# blank_rev_1.net
KiCad netlist of a schematic drawn in EAGLE
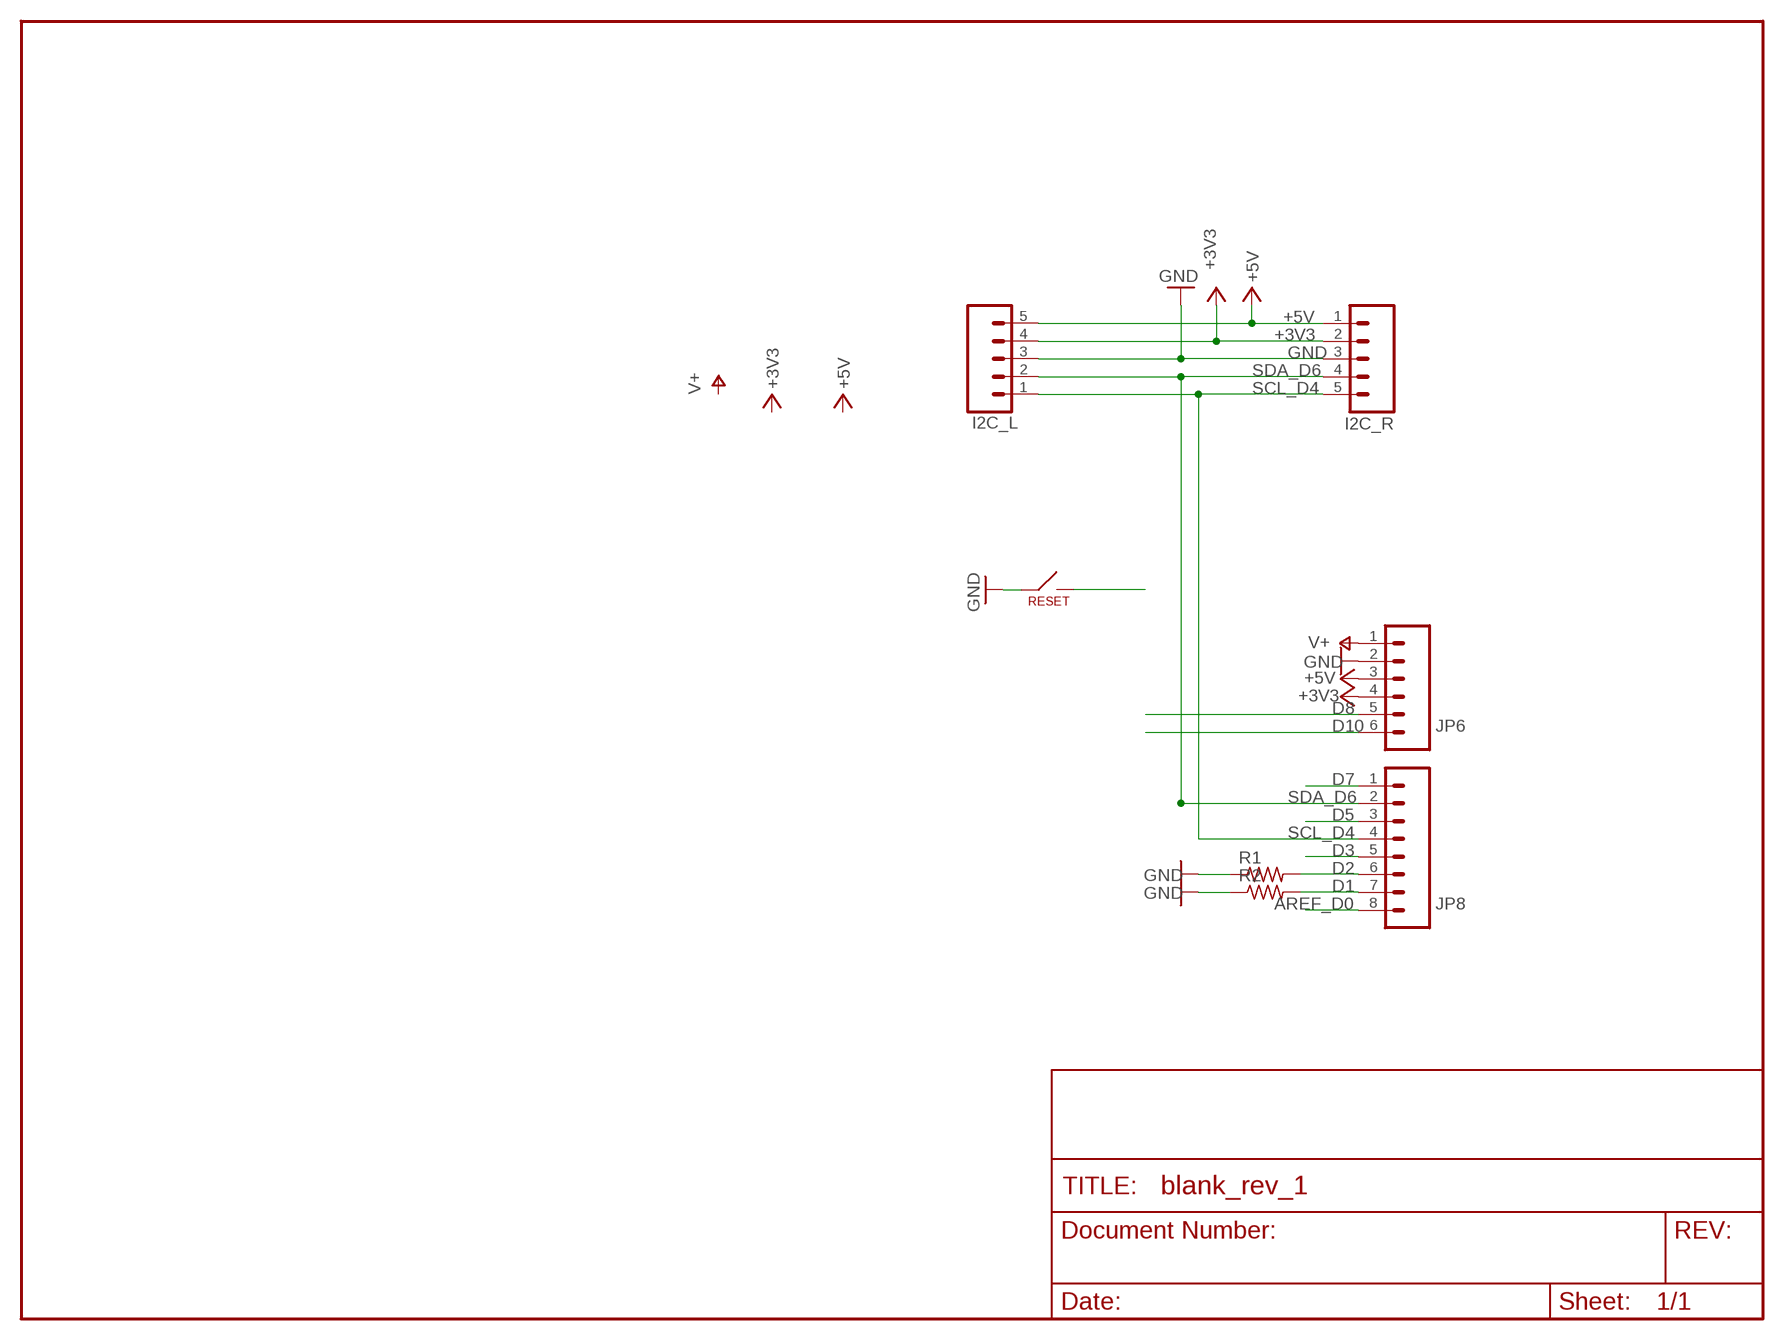
[diagram p0: schematic, sheet 1]

(export (version "E")
  (design (tool "Eeschema 10.0.6"))
  (components
    (comp (ref "I2C_L")
      (value "M05PTH")
      (footprint "eagle-import:1X05")
      (libsource (lib "eagle-import") (part "M05PTH"))
    )
    (comp (ref "I2C_R")
      (value "M05PTH")
      (footprint "eagle-import:1X05")
      (libsource (lib "eagle-import") (part "M05PTH"))
    )
    (comp (ref "JP6")
      (value "M06SIP")
      (footprint "eagle-import:1X06")
      (libsource (lib "eagle-import") (part "M06SIP"))
    )
    (comp (ref "JP8")
      (value "M081X08")
      (footprint "eagle-import:1X08")
      (libsource (lib "eagle-import") (part "M081X08"))
    )
    (comp (ref "R1")
      (value "R-US_0204/2V")
      (footprint "eagle-import:0204V")
      (libsource (lib "eagle-import") (part "R-US_0204/2V"))
    )
    (comp (ref "R2")
      (value "R-US_0204/2V")
      (footprint "eagle-import:0204V")
      (libsource (lib "eagle-import") (part "R-US_0204/2V"))
    )
    (comp (ref "RESET")
      (value "PTS635_SWITCH")
      (footprint "eagle-import:PTS635_SWITCH")
      (libsource (lib "eagle-import") (part "PTS635_SWITCH"))
    )
  )
  (nets
    (net (code "1") (name "+3V3") (class "Default")
      (node (ref "I2C_L") (pin "4") (pinfunction "4_4") (pintype "passive"))
      (node (ref "I2C_R") (pin "2") (pinfunction "2_2") (pintype "passive"))
      (node (ref "JP6") (pin "4") (pinfunction "4_4") (pintype "passive"))
    )
    (net (code "2") (name "+5V") (class "Default")
      (node (ref "I2C_L") (pin "5") (pinfunction "5_5") (pintype "passive"))
      (node (ref "I2C_R") (pin "1") (pinfunction "1_1") (pintype "passive"))
      (node (ref "JP6") (pin "3") (pinfunction "3_3") (pintype "passive"))
    )
    (net (code "3") (name "/AREF_D0") (class "Default")
      (node (ref "JP8") (pin "8") (pinfunction "8_8") (pintype "passive"))
    )
    (net (code "4") (name "/D1") (class "Default")
      (node (ref "JP8") (pin "7") (pinfunction "7_7") (pintype "passive"))
      (node (ref "R2") (pin "2") (pinfunction "2_2") (pintype "passive"))
    )
    (net (code "5") (name "/D2") (class "Default")
      (node (ref "JP8") (pin "6") (pinfunction "6_6") (pintype "passive"))
      (node (ref "R1") (pin "2") (pinfunction "2_2") (pintype "passive"))
    )
    (net (code "6") (name "/D3") (class "Default")
      (node (ref "JP8") (pin "5") (pinfunction "5_5") (pintype "passive"))
    )
    (net (code "7") (name "/D5") (class "Default")
      (node (ref "JP8") (pin "3") (pinfunction "3_3") (pintype "passive"))
    )
    (net (code "8") (name "/D7") (class "Default")
      (node (ref "JP8") (pin "1") (pinfunction "1_1") (pintype "passive"))
    )
    (net (code "9") (name "/D8") (class "Default")
      (node (ref "JP6") (pin "5") (pinfunction "5_5") (pintype "passive"))
    )
    (net (code "10") (name "/D10") (class "Default")
      (node (ref "JP6") (pin "6") (pinfunction "6_6") (pintype "passive"))
    )
    (net (code "11") (name "/SCL_D4") (class "Default")
      (node (ref "I2C_L") (pin "1") (pinfunction "1_1") (pintype "passive"))
      (node (ref "I2C_R") (pin "5") (pinfunction "5_5") (pintype "passive"))
      (node (ref "JP8") (pin "4") (pinfunction "4_4") (pintype "passive"))
    )
    (net (code "12") (name "/SDA_D6") (class "Default")
      (node (ref "I2C_L") (pin "2") (pinfunction "2_2") (pintype "passive"))
      (node (ref "I2C_R") (pin "4") (pinfunction "4_4") (pintype "passive"))
      (node (ref "JP8") (pin "2") (pinfunction "2_2") (pintype "passive"))
    )
    (net (code "13") (name "GND") (class "Default")
      (node (ref "I2C_L") (pin "3") (pinfunction "3_3") (pintype "passive"))
      (node (ref "I2C_R") (pin "3") (pinfunction "3_3") (pintype "passive"))
      (node (ref "JP6") (pin "2") (pinfunction "2_2") (pintype "passive"))
      (node (ref "R1") (pin "1") (pinfunction "1_1") (pintype "passive"))
      (node (ref "R2") (pin "1") (pinfunction "1_1") (pintype "passive"))
      (node (ref "RESET") (pin "P$1") (pinfunction "P$1_P$1") (pintype "bidirectional"))
    )
    (net (code "14") (name "V+") (class "Default")
      (node (ref "JP6") (pin "1") (pinfunction "1_1") (pintype "passive"))
    )
    (net (code "15") (name "unconnected-(RESET-PadP$2)") (class "Default")
      (node (ref "RESET") (pin "P$2") (pinfunction "P$2_P$2") (pintype "bidirectional"))
    )
  )
)
